# control.net
KiCad netlist of a schematic drawn in Altium Designer
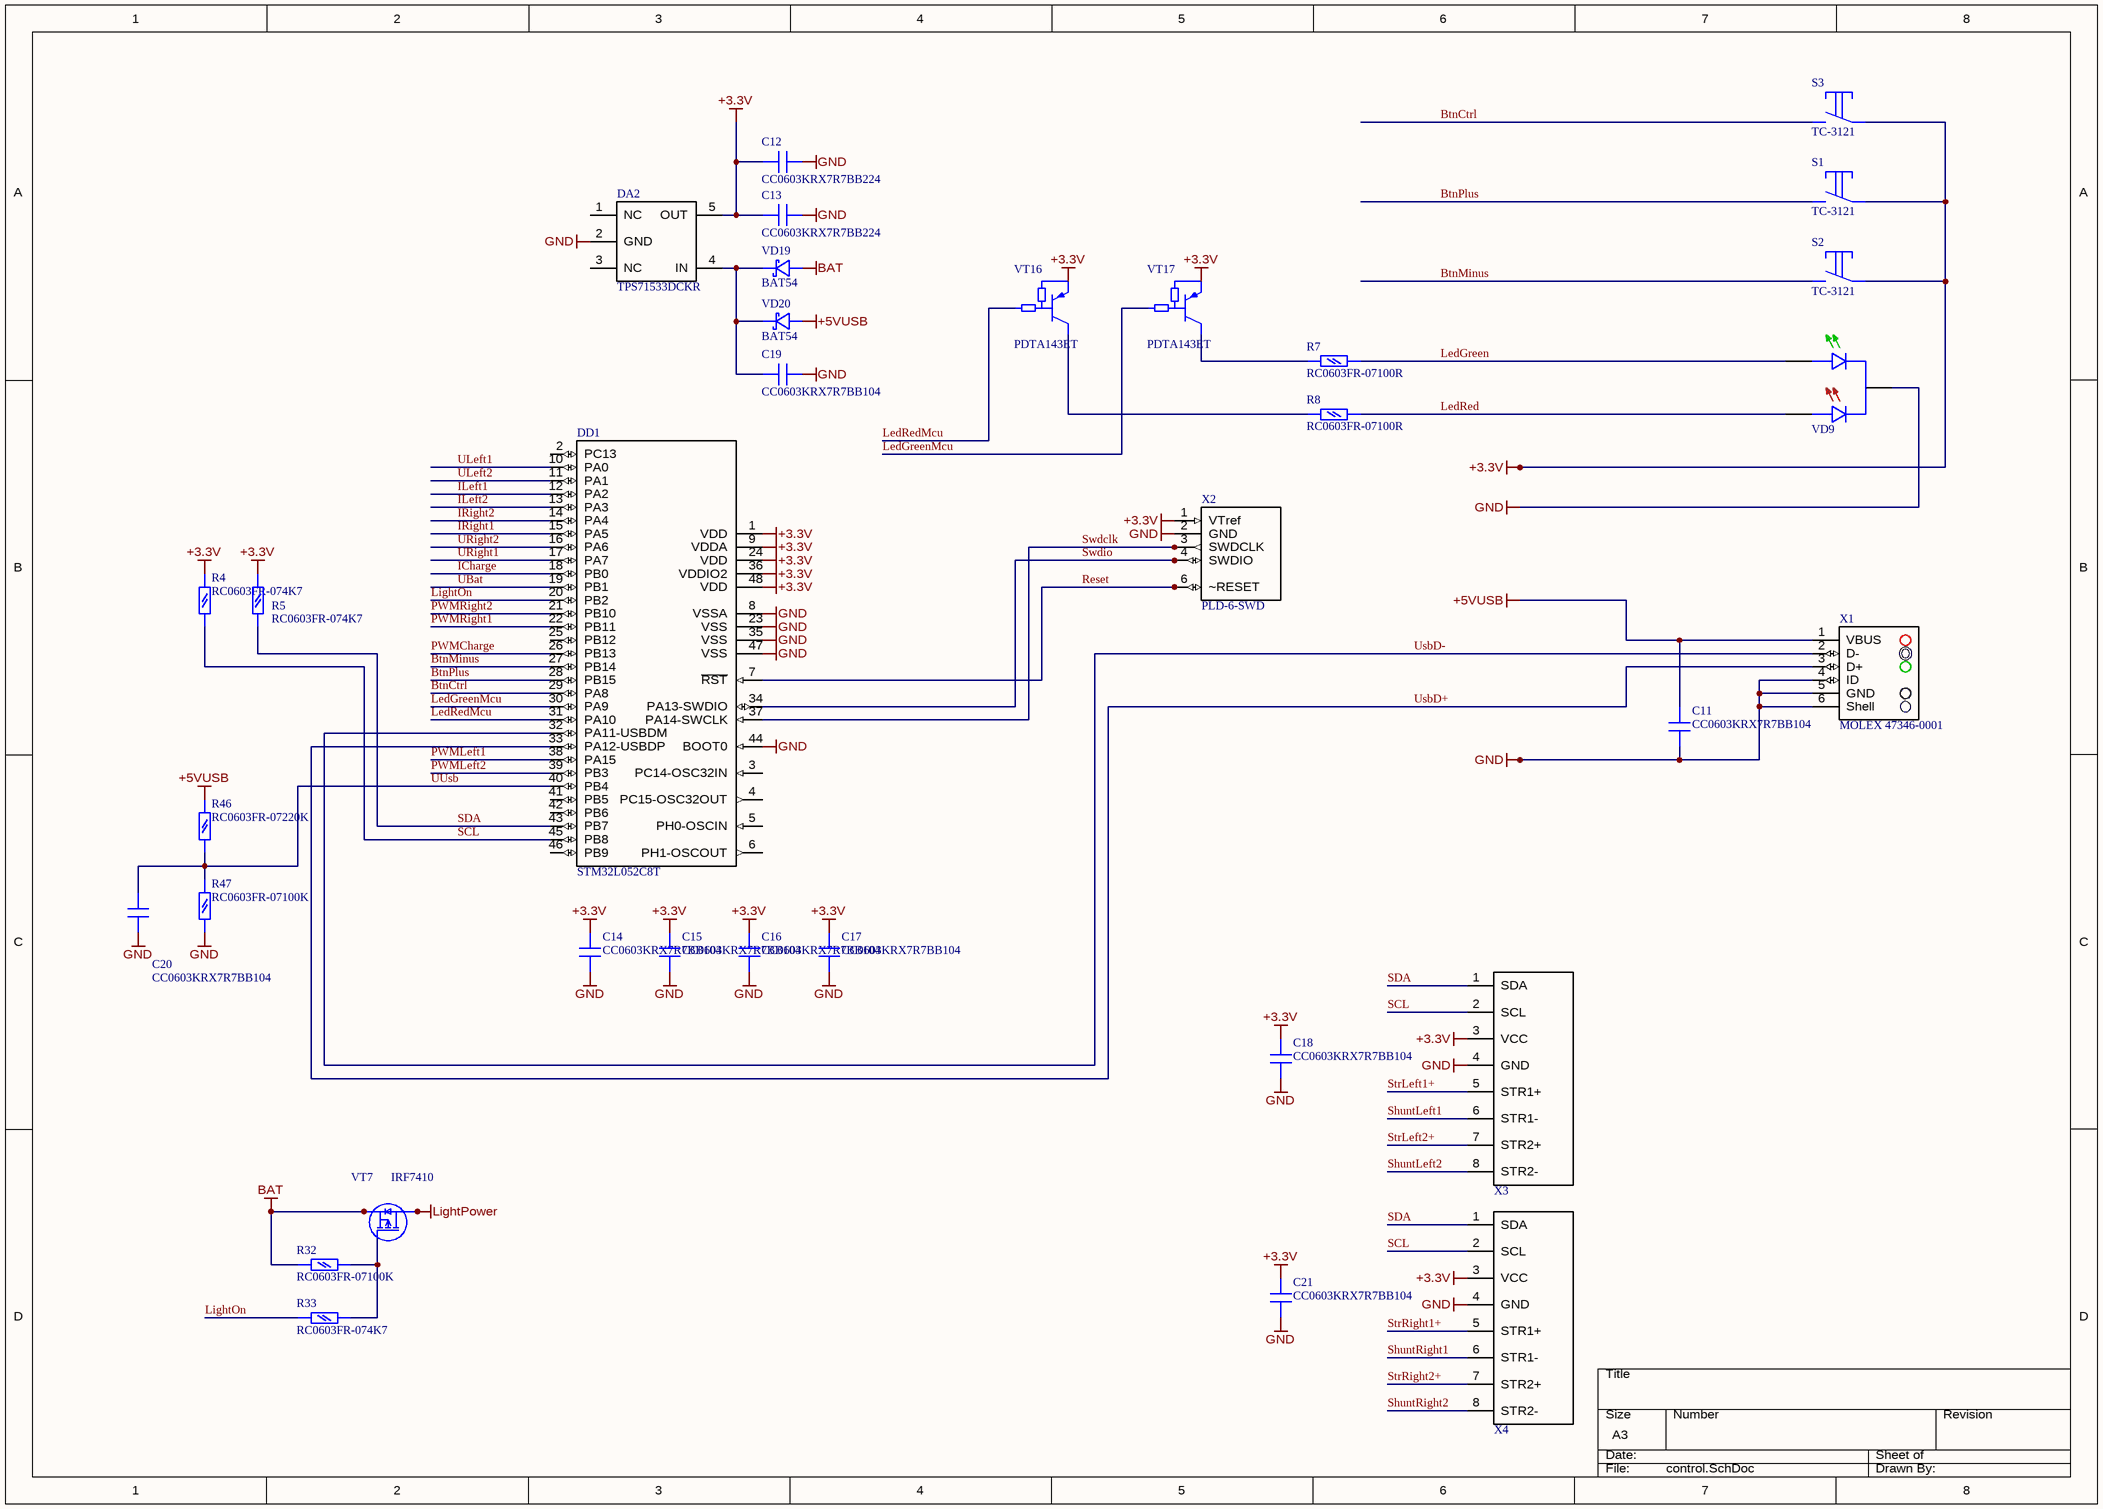
[diagram p0: control.SchDoc]

(export (version "E")
  (design (tool "Eeschema 10.0.6"))
  (components
    (comp (ref "C11")
      (value "CC0603KRX7R7BB104")
      (footprint "CapacitorSMD0603(manual)")
      (description "CAPACITOR Capacitor SMD 0603 1.6x0.8mm")
      (libsource (lib "Integrated_Library") (part "CapacitorSMD0603(reflow)"))
    )
    (comp (ref "C12")
      (value "CC0603KRX7R7BB224")
      (footprint "CapacitorSMD0603(manual)")
      (description "CAPACITOR Capacitor SMD 0603 1.6x0.8mm")
      (libsource (lib "Integrated_Library") (part "CapacitorSMD0603(reflow)"))
    )
    (comp (ref "C13")
      (value "CC0603KRX7R7BB224")
      (footprint "CapacitorSMD0603(manual)")
      (description "CAPACITOR Capacitor SMD 0603 1.6x0.8mm")
      (libsource (lib "Integrated_Library") (part "CapacitorSMD0603(reflow)"))
    )
    (comp (ref "C14")
      (value "CC0603KRX7R7BB104")
      (footprint "CapacitorSMD0603(manual)")
      (description "CAPACITOR Capacitor SMD 0603 1.6x0.8mm")
      (libsource (lib "Integrated_Library") (part "CapacitorSMD0603(reflow)"))
    )
    (comp (ref "C15")
      (value "CC0603KRX7R7BB104")
      (footprint "CapacitorSMD0603(manual)")
      (description "CAPACITOR Capacitor SMD 0603 1.6x0.8mm")
      (libsource (lib "Integrated_Library") (part "CapacitorSMD0603(reflow)"))
    )
    (comp (ref "C16")
      (value "CC0603KRX7R7BB104")
      (footprint "CapacitorSMD0603(manual)")
      (description "CAPACITOR Capacitor SMD 0603 1.6x0.8mm")
      (libsource (lib "Integrated_Library") (part "CapacitorSMD0603(reflow)"))
    )
    (comp (ref "C17")
      (value "CC0603KRX7R7BB104")
      (footprint "CapacitorSMD0603(manual)")
      (description "CAPACITOR Capacitor SMD 0603 1.6x0.8mm")
      (libsource (lib "Integrated_Library") (part "CapacitorSMD0603(reflow)"))
    )
    (comp (ref "C18")
      (value "CC0603KRX7R7BB104")
      (footprint "CapacitorSMD0603(manual)")
      (description "CAPACITOR Capacitor SMD 0603 1.6x0.8mm")
      (libsource (lib "Integrated_Library") (part "CapacitorSMD0603(reflow)"))
    )
    (comp (ref "C19")
      (value "CC0603KRX7R7BB104")
      (footprint "CapacitorSMD0603(manual)")
      (description "CAPACITOR Capacitor SMD 0603 1.6x0.8mm")
      (libsource (lib "Integrated_Library") (part "CapacitorSMD0603(reflow)"))
    )
    (comp (ref "C20")
      (value "CC0603KRX7R7BB104")
      (footprint "CapacitorSMD0603(manual)")
      (description "CAPACITOR Capacitor SMD 0603 1.6x0.8mm")
      (libsource (lib "Integrated_Library") (part "CapacitorSMD0603(reflow)"))
    )
    (comp (ref "C21")
      (value "CC0603KRX7R7BB104")
      (footprint "CapacitorSMD0603(manual)")
      (description "CAPACITOR Capacitor SMD 0603 1.6x0.8mm")
      (libsource (lib "Integrated_Library") (part "CapacitorSMD0603(reflow)"))
    )
    (comp (ref "DA2")
      (value "TPS71533DCKR")
      (footprint "SOT323-5")
      (description "IC LDO")
      (libsource (lib "Integrated_Library") (part "TPS715__DCKR"))
    )
    (comp (ref "DD1")
      (value "STM32L052C8T")
      (footprint "LQFP48_STM32")
      (description "IC UC/UP")
      (libsource (lib "Integrated_Library") (part "STM32L052C_T"))
    )
    (comp (ref "R4")
      (value "RC0603FR-074K7")
      (footprint "ResistorSMD0603(manual)")
      (description "RESISTOR Resistor SMD 0603 1.6x0.8mm")
      (libsource (lib "Integrated_Library") (part "ResistorSMD0603(reflow)"))
    )
    (comp (ref "R5")
      (value "RC0603FR-074K7")
      (footprint "ResistorSMD0603(manual)")
      (description "RESISTOR Resistor SMD 0603 1.6x0.8mm")
      (libsource (lib "Integrated_Library") (part "ResistorSMD0603(reflow)"))
    )
    (comp (ref "R7")
      (value "RC0603FR-07100R")
      (footprint "ResistorSMD0603(manual)")
      (description "RESISTOR Resistor SMD 0603 1.6x0.8mm")
      (libsource (lib "Integrated_Library") (part "ResistorSMD0603(reflow)"))
    )
    (comp (ref "R8")
      (value "RC0603FR-07100R")
      (footprint "ResistorSMD0603(manual)")
      (description "RESISTOR Resistor SMD 0603 1.6x0.8mm")
      (libsource (lib "Integrated_Library") (part "ResistorSMD0603(reflow)"))
    )
    (comp (ref "R32")
      (value "RC0603FR-07100K")
      (footprint "ResistorSMD0603(manual)")
      (description "RESISTOR Resistor SMD 0603 1.6x0.8mm")
      (libsource (lib "Integrated_Library") (part "ResistorSMD0603(reflow)"))
    )
    (comp (ref "R33")
      (value "RC0603FR-074K7")
      (footprint "ResistorSMD0603(manual)")
      (description "RESISTOR Resistor SMD 0603 1.6x0.8mm")
      (libsource (lib "Integrated_Library") (part "ResistorSMD0603(reflow)"))
    )
    (comp (ref "R46")
      (value "RC0603FR-07220K")
      (footprint "ResistorSMD0603(manual)")
      (description "RESISTOR Resistor SMD 0603 1.6x0.8mm")
      (libsource (lib "Integrated_Library") (part "ResistorSMD0603(reflow)"))
    )
    (comp (ref "R47")
      (value "RC0603FR-07100K")
      (footprint "ResistorSMD0603(manual)")
      (description "RESISTOR Resistor SMD 0603 1.6x0.8mm")
      (libsource (lib "Integrated_Library") (part "ResistorSMD0603(reflow)"))
    )
    (comp (ref "S1")
      (value "TC-3121")
      (footprint "TC-3121(right-angle var1)")
      (description "SWITCH Button")
      (libsource (lib "Integrated_Library") (part "TC-3121"))
    )
    (comp (ref "S2")
      (value "TC-3121")
      (footprint "TC-3121(right-angle var1)")
      (description "SWITCH Button")
      (libsource (lib "Integrated_Library") (part "TC-3121"))
    )
    (comp (ref "S3")
      (value "TC-3121")
      (footprint "TC-3121(right-angle var1)")
      (description "SWITCH Button")
      (libsource (lib "Integrated_Library") (part "TC-3121"))
    )
    (comp (ref "VD9")
      (value "L-119EGWT")
      (footprint "L-119EGWT(rightAngleVar1)")
      (description "Right-angle red/green LED")
      (libsource (lib "Integrated_Library") (part "L-119EGWT"))
    )
    (comp (ref "VD19")
      (value "BAT54")
      (footprint "SOT23")
      (description "DIODE Schottky barrier diodes")
      (libsource (lib "Integrated_Library") (part "BAT54"))
    )
    (comp (ref "VD20")
      (value "BAT54")
      (footprint "SOT23")
      (description "DIODE Schottky barrier diodes")
      (libsource (lib "Integrated_Library") (part "BAT54"))
    )
    (comp (ref "VT7")
      (value "IRF7410")
      (footprint "SO8")
      (description "TRANSISTOR MOSFET P generic SO8")
      (libsource (lib "Integrated_Library") (part "MOSFET_P_SO8"))
    )
    (comp (ref "VT16")
      (value "PDTA143ET")
      (footprint "SOT23")
      (description "TRANSISTOR PNP resistors-equipped transistor sot23")
      (libsource (lib "CompleteLibrary") (part "PDTA143ET"))
    )
    (comp (ref "VT17")
      (value "PDTA143ET")
      (footprint "SOT23")
      (description "TRANSISTOR PNP resistors-equipped transistor sot23")
      (libsource (lib "CompleteLibrary") (part "PDTA143ET"))
    )
    (comp (ref "X1")
      (value "MOLEX 47346-0001")
      (footprint "MOLEX 47346-0001")
      (description "CONNECTOR USB micro B")
      (libsource (lib "Integrated_Library") (part "MOLEX 47346-0001"))
    )
    (comp (ref "X2")
      (value "PLD-6-SWD")
      (footprint "PLD-6-SWD")
      (description "CONNECTOR PROGRAM 6-pin SWD connector")
      (libsource (lib "Connectors") (part "PLD-6-SWD"))
    )
    (comp (ref "X3")
      (value "ConnectorMainSide")
      (footprint "ConnectorMainSide")
      (libsource (lib "MBLv1") (part "ConnectorMainSide"))
    )
    (comp (ref "X4")
      (value "ConnectorMainSide")
      (footprint "ConnectorMainSide")
      (libsource (lib "MBLv1") (part "ConnectorMainSide"))
    )
  )
  (nets
    (net (code "1") (name "+3.3V") (class "Default")
      (node (ref "C12") (pin "2") (pintype "passive"))
      (node (ref "C13") (pin "2") (pintype "passive"))
      (node (ref "C14") (pin "2") (pintype "passive"))
      (node (ref "C15") (pin "2") (pintype "passive"))
      (node (ref "C16") (pin "2") (pintype "passive"))
      (node (ref "C17") (pin "2") (pintype "passive"))
      (node (ref "C18") (pin "2") (pintype "passive"))
      (node (ref "C21") (pin "2") (pintype "passive"))
      (node (ref "DA2") (pin "5") (pinfunction "OUT_5") (pintype "passive"))
      (node (ref "DD1") (pin "1") (pinfunction "VDD_1") (pintype "power_in"))
      (node (ref "DD1") (pin "24") (pinfunction "VDD_24") (pintype "power_in"))
      (node (ref "DD1") (pin "36") (pinfunction "VDDIO2_36") (pintype "power_in"))
      (node (ref "DD1") (pin "48") (pinfunction "VDD_48") (pintype "power_in"))
      (node (ref "DD1") (pin "9") (pinfunction "VDDA_9") (pintype "power_in"))
      (node (ref "R4") (pin "1") (pinfunction "1_1") (pintype "passive"))
      (node (ref "R5") (pin "1") (pinfunction "1_1") (pintype "passive"))
      (node (ref "S1") (pin "2") (pintype "passive"))
      (node (ref "S2") (pin "2") (pintype "passive"))
      (node (ref "S3") (pin "2") (pintype "passive"))
      (node (ref "VT16") (pin "2") (pinfunction "2_2") (pintype "passive"))
      (node (ref "VT17") (pin "2") (pinfunction "2_2") (pintype "passive"))
      (node (ref "X2") (pin "1") (pinfunction "VTref_1") (pintype "input"))
      (node (ref "X3") (pin "3") (pinfunction "VCC_3") (pintype "passive"))
      (node (ref "X4") (pin "3") (pinfunction "VCC_3") (pintype "passive"))
    )
    (net (code "2") (name "+5VUSB") (class "Default")
      (node (ref "C11") (pin "2") (pintype "passive"))
      (node (ref "R46") (pin "1") (pinfunction "1_1") (pintype "passive"))
      (node (ref "VD20") (pin "1") (pintype "passive"))
      (node (ref "X1") (pin "1") (pinfunction "VBUS_1") (pintype "power_in"))
    )
    (net (code "3") (name "/BtnCtrl") (class "Default")
      (node (ref "DD1") (pin "29") (pinfunction "PA8_29") (pintype "bidirectional"))
      (node (ref "S3") (pin "1") (pintype "passive"))
    )
    (net (code "4") (name "/BtnMinus") (class "Default")
      (node (ref "DD1") (pin "27") (pinfunction "PB14_27") (pintype "bidirectional"))
      (node (ref "S2") (pin "1") (pintype "passive"))
    )
    (net (code "5") (name "/BtnPlus") (class "Default")
      (node (ref "DD1") (pin "28") (pinfunction "PB15_28") (pintype "bidirectional"))
      (node (ref "S1") (pin "1") (pintype "passive"))
    )
    (net (code "6") (name "/ICharge") (class "Default")
      (node (ref "DD1") (pin "18") (pinfunction "PB0_18") (pintype "bidirectional"))
    )
    (net (code "7") (name "/ILeft1") (class "Default")
      (node (ref "DD1") (pin "12") (pinfunction "PA2_12") (pintype "bidirectional"))
    )
    (net (code "8") (name "/ILeft2") (class "Default")
      (node (ref "DD1") (pin "13") (pinfunction "PA3_13") (pintype "bidirectional"))
    )
    (net (code "9") (name "/IRight1") (class "Default")
      (node (ref "DD1") (pin "15") (pinfunction "PA5_15") (pintype "bidirectional"))
    )
    (net (code "10") (name "/IRight2") (class "Default")
      (node (ref "DD1") (pin "14") (pinfunction "PA4_14") (pintype "bidirectional"))
    )
    (net (code "11") (name "/LedGreen") (class "Default")
      (node (ref "R7") (pin "2") (pinfunction "2_2") (pintype "passive"))
      (node (ref "VD9") (pin "3") (pintype "passive"))
    )
    (net (code "12") (name "/LedGreenMcu") (class "Default")
      (node (ref "DD1") (pin "30") (pinfunction "PA9_30") (pintype "bidirectional"))
      (node (ref "VT17") (pin "1") (pinfunction "1_1") (pintype "passive"))
    )
    (net (code "13") (name "/LedRed") (class "Default")
      (node (ref "R8") (pin "2") (pinfunction "2_2") (pintype "passive"))
      (node (ref "VD9") (pin "1") (pintype "passive"))
    )
    (net (code "14") (name "/LedRedMcu") (class "Default")
      (node (ref "DD1") (pin "31") (pinfunction "PA10_31") (pintype "bidirectional"))
      (node (ref "VT16") (pin "1") (pinfunction "1_1") (pintype "passive"))
    )
    (net (code "15") (name "/LightOn") (class "Default")
      (node (ref "DD1") (pin "20") (pinfunction "PB2_20") (pintype "bidirectional"))
      (node (ref "R33") (pin "2") (pinfunction "2_2") (pintype "passive"))
    )
    (net (code "16") (name "/PWMCharge") (class "Default")
      (node (ref "DD1") (pin "26") (pinfunction "PB13_26") (pintype "bidirectional"))
    )
    (net (code "17") (name "/PWMLeft1") (class "Default")
      (node (ref "DD1") (pin "38") (pinfunction "PA15_38") (pintype "bidirectional"))
    )
    (net (code "18") (name "/PWMLeft2") (class "Default")
      (node (ref "DD1") (pin "39") (pinfunction "PB3_39") (pintype "bidirectional"))
    )
    (net (code "19") (name "/PWMRight1") (class "Default")
      (node (ref "DD1") (pin "22") (pinfunction "PB11_22") (pintype "bidirectional"))
    )
    (net (code "20") (name "/PWMRight2") (class "Default")
      (node (ref "DD1") (pin "21") (pinfunction "PB10_21") (pintype "bidirectional"))
    )
    (net (code "21") (name "/Reset") (class "Default")
      (node (ref "DD1") (pin "7") (pinfunction "~{RST}_7") (pintype "input"))
      (node (ref "X2") (pin "6") (pinfunction "~RESET_6") (pintype "bidirectional"))
    )
    (net (code "22") (name "/SCL") (class "Default")
      (node (ref "DD1") (pin "45") (pinfunction "PB8_45") (pintype "bidirectional"))
      (node (ref "R4") (pin "2") (pinfunction "2_2") (pintype "passive"))
      (node (ref "X3") (pin "2") (pinfunction "SCL_2") (pintype "passive"))
      (node (ref "X4") (pin "2") (pinfunction "SCL_2") (pintype "passive"))
    )
    (net (code "23") (name "/SDA") (class "Default")
      (node (ref "DD1") (pin "43") (pinfunction "PB7_43") (pintype "bidirectional"))
      (node (ref "R5") (pin "2") (pinfunction "2_2") (pintype "passive"))
      (node (ref "X3") (pin "1") (pinfunction "SDA_1") (pintype "passive"))
      (node (ref "X4") (pin "1") (pinfunction "SDA_1") (pintype "passive"))
    )
    (net (code "24") (name "/ShuntLeft1") (class "Default")
      (node (ref "X3") (pin "6") (pinfunction "STR1-_6") (pintype "passive"))
    )
    (net (code "25") (name "/ShuntLeft2") (class "Default")
      (node (ref "X3") (pin "8") (pinfunction "STR2-_8") (pintype "passive"))
    )
    (net (code "26") (name "/ShuntRight1") (class "Default")
      (node (ref "X4") (pin "6") (pinfunction "STR1-_6") (pintype "passive"))
    )
    (net (code "27") (name "/ShuntRight2") (class "Default")
      (node (ref "X4") (pin "8") (pinfunction "STR2-_8") (pintype "passive"))
    )
    (net (code "28") (name "/StrLeft1+") (class "Default")
      (node (ref "X3") (pin "5") (pinfunction "STR1+_5") (pintype "passive"))
    )
    (net (code "29") (name "/StrLeft2+") (class "Default")
      (node (ref "X3") (pin "7") (pinfunction "STR2+_7") (pintype "passive"))
    )
    (net (code "30") (name "/StrRight1+") (class "Default")
      (node (ref "X4") (pin "5") (pinfunction "STR1+_5") (pintype "passive"))
    )
    (net (code "31") (name "/StrRight2+") (class "Default")
      (node (ref "X4") (pin "7") (pinfunction "STR2+_7") (pintype "passive"))
    )
    (net (code "32") (name "/Swdclk") (class "Default")
      (node (ref "DD1") (pin "37") (pinfunction "PA14-SWCLK_37") (pintype "input"))
      (node (ref "X2") (pin "3") (pinfunction "SWDCLK_3") (pintype "output"))
    )
    (net (code "33") (name "/Swdio") (class "Default")
      (node (ref "DD1") (pin "34") (pinfunction "PA13-SWDIO_34") (pintype "bidirectional"))
      (node (ref "X2") (pin "4") (pinfunction "SWDIO_4") (pintype "bidirectional"))
    )
    (net (code "34") (name "/UBat") (class "Default")
      (node (ref "DD1") (pin "19") (pinfunction "PB1_19") (pintype "bidirectional"))
    )
    (net (code "35") (name "/ULeft1") (class "Default")
      (node (ref "DD1") (pin "10") (pinfunction "PA0_10") (pintype "bidirectional"))
    )
    (net (code "36") (name "/ULeft2") (class "Default")
      (node (ref "DD1") (pin "11") (pinfunction "PA1_11") (pintype "bidirectional"))
    )
    (net (code "37") (name "/URight1") (class "Default")
      (node (ref "DD1") (pin "17") (pinfunction "PA7_17") (pintype "bidirectional"))
    )
    (net (code "38") (name "/URight2") (class "Default")
      (node (ref "DD1") (pin "16") (pinfunction "PA6_16") (pintype "bidirectional"))
    )
    (net (code "39") (name "/UUsb") (class "Default")
      (node (ref "C20") (pin "1") (pintype "passive"))
      (node (ref "DD1") (pin "40") (pinfunction "PB4_40") (pintype "bidirectional"))
      (node (ref "R46") (pin "2") (pinfunction "2_2") (pintype "passive"))
      (node (ref "R47") (pin "1") (pinfunction "1_1") (pintype "passive"))
    )
    (net (code "40") (name "/UsbD+") (class "Default")
      (node (ref "DD1") (pin "33") (pinfunction "PA12-USBDP_33") (pintype "bidirectional"))
      (node (ref "X1") (pin "3") (pinfunction "D+_3") (pintype "bidirectional"))
    )
    (net (code "41") (name "/UsbD-") (class "Default")
      (node (ref "DD1") (pin "32") (pinfunction "PA11-USBDM_32") (pintype "bidirectional"))
      (node (ref "X1") (pin "2") (pinfunction "D-_2") (pintype "bidirectional"))
    )
    (net (code "42") (name "BAT") (class "Default")
      (node (ref "R32") (pin "2") (pinfunction "2_2") (pintype "passive"))
      (node (ref "VD19") (pin "1") (pintype "passive"))
      (node (ref "VT7") (pin "1") (pinfunction "S_1") (pintype "passive"))
      (node (ref "VT7") (pin "2") (pinfunction "S_2") (pintype "passive"))
      (node (ref "VT7") (pin "3") (pinfunction "S_3") (pintype "passive"))
    )
    (net (code "43") (name "GND") (class "Default")
      (node (ref "C11") (pin "1") (pintype "passive"))
      (node (ref "C12") (pin "1") (pintype "passive"))
      (node (ref "C13") (pin "1") (pintype "passive"))
      (node (ref "C14") (pin "1") (pintype "passive"))
      (node (ref "C15") (pin "1") (pintype "passive"))
      (node (ref "C16") (pin "1") (pintype "passive"))
      (node (ref "C17") (pin "1") (pintype "passive"))
      (node (ref "C18") (pin "1") (pintype "passive"))
      (node (ref "C19") (pin "1") (pintype "passive"))
      (node (ref "C20") (pin "2") (pintype "passive"))
      (node (ref "C21") (pin "1") (pintype "passive"))
      (node (ref "DA2") (pin "2") (pinfunction "GND_2") (pintype "passive"))
      (node (ref "DD1") (pin "23") (pinfunction "VSS_23") (pintype "power_in"))
      (node (ref "DD1") (pin "35") (pinfunction "VSS_35") (pintype "power_in"))
      (node (ref "DD1") (pin "44") (pinfunction "BOOT0_44") (pintype "input"))
      (node (ref "DD1") (pin "47") (pinfunction "VSS_47") (pintype "power_in"))
      (node (ref "DD1") (pin "8") (pinfunction "VSSA_8") (pintype "power_in"))
      (node (ref "R47") (pin "2") (pinfunction "2_2") (pintype "passive"))
      (node (ref "VD9") (pin "2") (pintype "passive"))
      (node (ref "X1") (pin "4") (pinfunction "ID_4") (pintype "bidirectional"))
      (node (ref "X1") (pin "5") (pinfunction "GND_5") (pintype "passive"))
      (node (ref "X1") (pin "6") (pinfunction "Shell_6") (pintype "passive"))
      (node (ref "X2") (pin "2") (pinfunction "GND_2") (pintype "power_in"))
      (node (ref "X3") (pin "4") (pinfunction "GND_4") (pintype "passive"))
      (node (ref "X4") (pin "4") (pinfunction "GND_4") (pintype "passive"))
    )
    (net (code "44") (name "LightPower") (class "Default")
      (node (ref "VT7") (pin "5") (pinfunction "D_5") (pintype "passive"))
      (node (ref "VT7") (pin "6") (pinfunction "D_6") (pintype "passive"))
      (node (ref "VT7") (pin "7") (pinfunction "D_7") (pintype "passive"))
      (node (ref "VT7") (pin "8") (pinfunction "D_8") (pintype "passive"))
    )
    (net (code "45") (name "Net-(DA2-IN)") (class "Default")
      (node (ref "C19") (pin "2") (pintype "passive"))
      (node (ref "DA2") (pin "4") (pinfunction "IN_4") (pintype "passive"))
      (node (ref "VD19") (pin "3") (pintype "passive"))
      (node (ref "VD20") (pin "3") (pintype "passive"))
    )
    (net (code "46") (name "Net-(R7-Pad1)") (class "Default")
      (node (ref "R7") (pin "1") (pinfunction "1_1") (pintype "passive"))
      (node (ref "VT17") (pin "3") (pinfunction "3_3") (pintype "passive"))
    )
    (net (code "47") (name "Net-(R8-Pad1)") (class "Default")
      (node (ref "R8") (pin "1") (pinfunction "1_1") (pintype "passive"))
      (node (ref "VT16") (pin "3") (pinfunction "3_3") (pintype "passive"))
    )
    (net (code "48") (name "Net-(VT7-G)") (class "Default")
      (node (ref "R32") (pin "1") (pinfunction "1_1") (pintype "passive"))
      (node (ref "R33") (pin "1") (pinfunction "1_1") (pintype "passive"))
      (node (ref "VT7") (pin "4") (pinfunction "G_4") (pintype "passive"))
    )
    (net (code "49") (name "unconnected-(DA2-NC-Pad1)") (class "Default")
      (node (ref "DA2") (pin "1") (pinfunction "NC_1") (pintype "passive"))
    )
    (net (code "50") (name "unconnected-(DA2-NC-Pad3)") (class "Default")
      (node (ref "DA2") (pin "3") (pinfunction "NC_3") (pintype "passive"))
    )
    (net (code "51") (name "unconnected-(DD1-PB5-Pad41)") (class "Default")
      (node (ref "DD1") (pin "41") (pinfunction "PB5_41") (pintype "bidirectional"))
    )
    (net (code "52") (name "unconnected-(DD1-PB6-Pad42)") (class "Default")
      (node (ref "DD1") (pin "42") (pinfunction "PB6_42") (pintype "bidirectional"))
    )
    (net (code "53") (name "unconnected-(DD1-PB9-Pad46)") (class "Default")
      (node (ref "DD1") (pin "46") (pinfunction "PB9_46") (pintype "bidirectional"))
    )
    (net (code "54") (name "unconnected-(DD1-PB12-Pad25)") (class "Default")
      (node (ref "DD1") (pin "25") (pinfunction "PB12_25") (pintype "bidirectional"))
    )
    (net (code "55") (name "unconnected-(DD1-PC13-Pad2)") (class "Default")
      (node (ref "DD1") (pin "2") (pinfunction "PC13_2") (pintype "bidirectional"))
    )
    (net (code "56") (name "unconnected-(DD1-PC14-OSC32IN-Pad3)") (class "Default")
      (node (ref "DD1") (pin "3") (pinfunction "PC14-OSC32IN_3") (pintype "input"))
    )
    (net (code "57") (name "unconnected-(DD1-PC15-OSC32OUT-Pad4)") (class "Default")
      (node (ref "DD1") (pin "4") (pinfunction "PC15-OSC32OUT_4") (pintype "output"))
    )
    (net (code "58") (name "unconnected-(DD1-PH0-OSCIN-Pad5)") (class "Default")
      (node (ref "DD1") (pin "5") (pinfunction "PH0-OSCIN_5") (pintype "input"))
    )
    (net (code "59") (name "unconnected-(DD1-PH1-OSCOUT-Pad6)") (class "Default")
      (node (ref "DD1") (pin "6") (pinfunction "PH1-OSCOUT_6") (pintype "output"))
    )
  )
)
